# con-som.net
KiCad netlist of a schematic drawn in Altium Designer
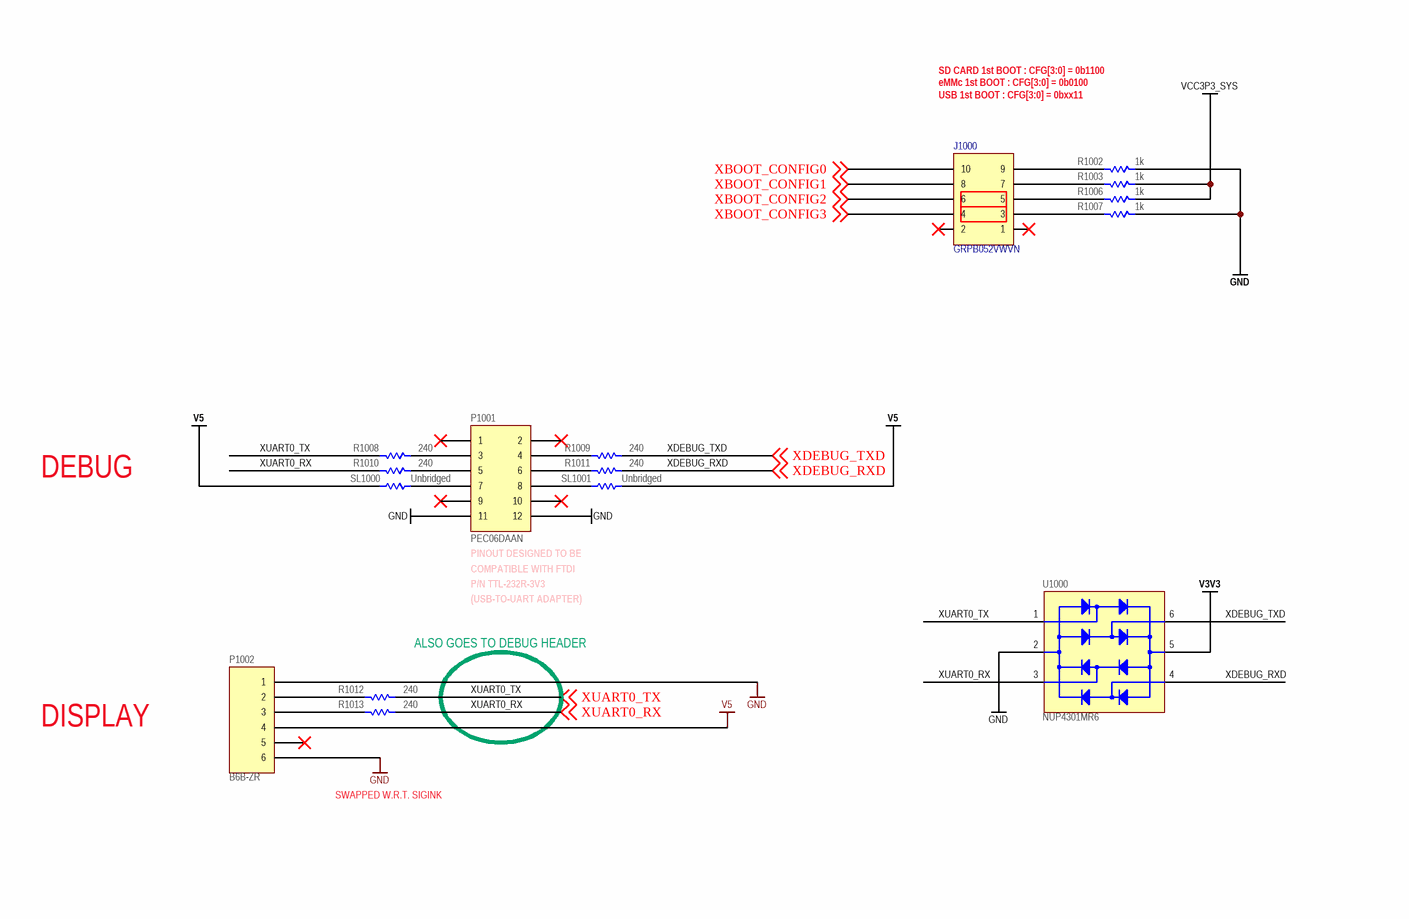
[diagram p0: con-som.SchDoc, top left]
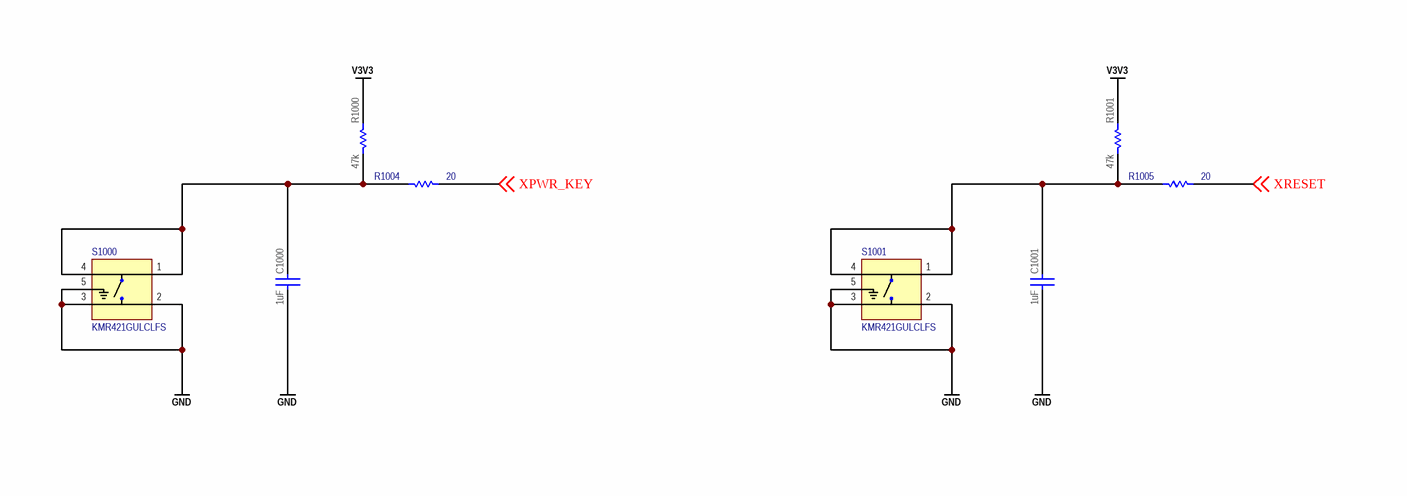
[diagram p1: con-som.SchDoc, top right]
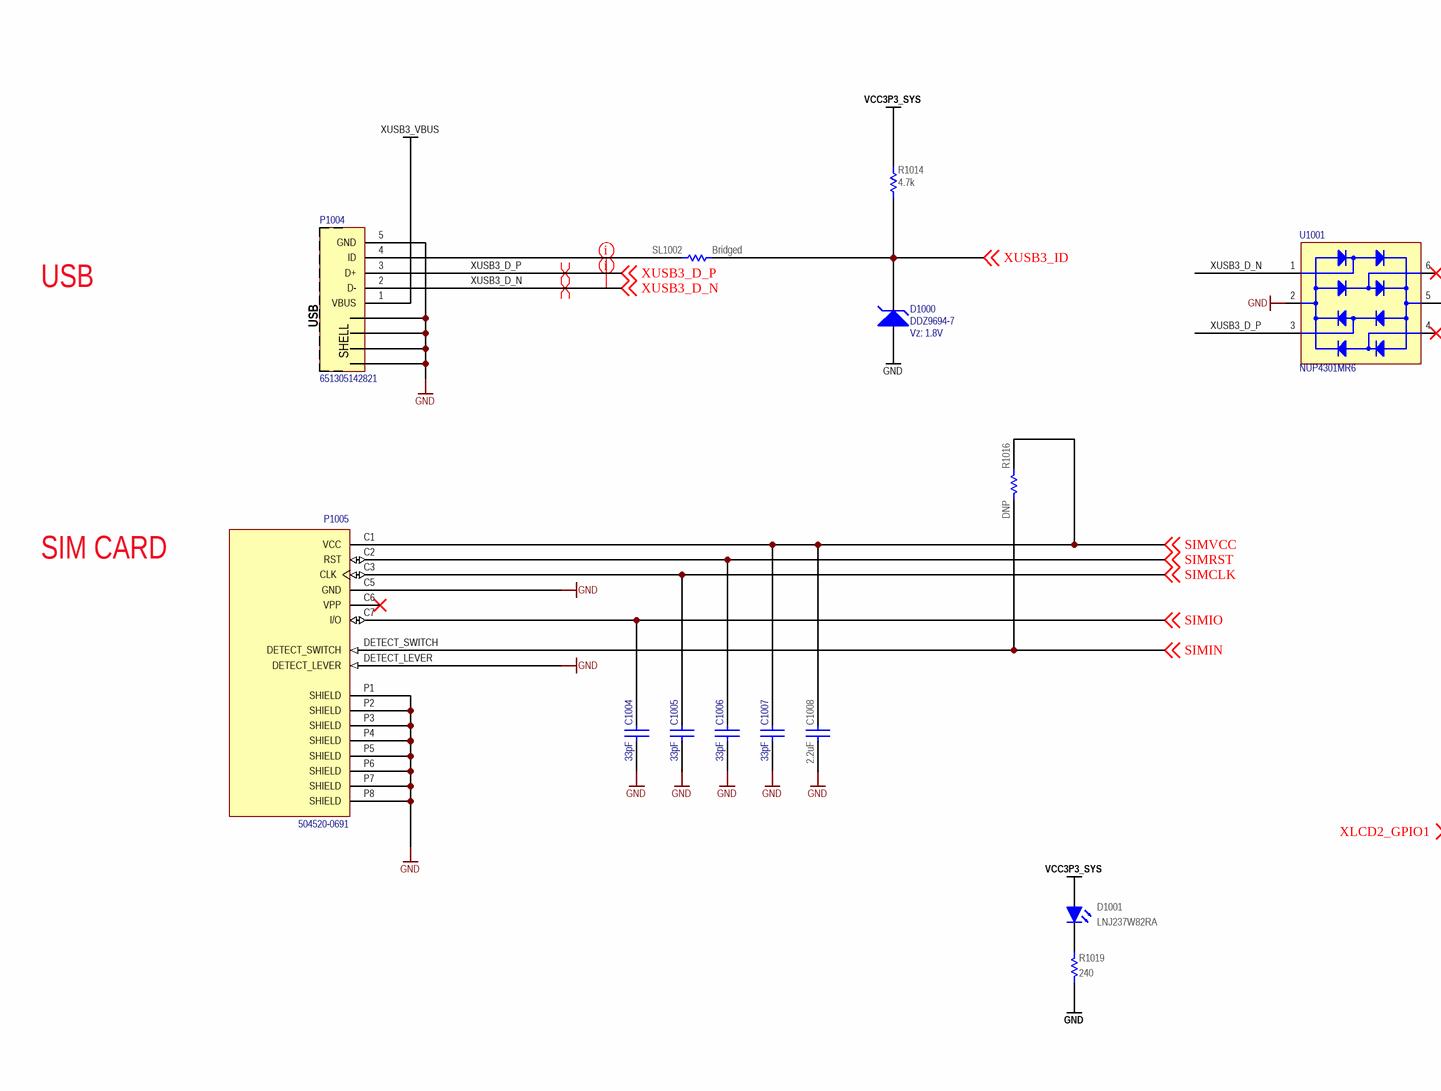
[diagram p2: con-som.SchDoc, bottom left]
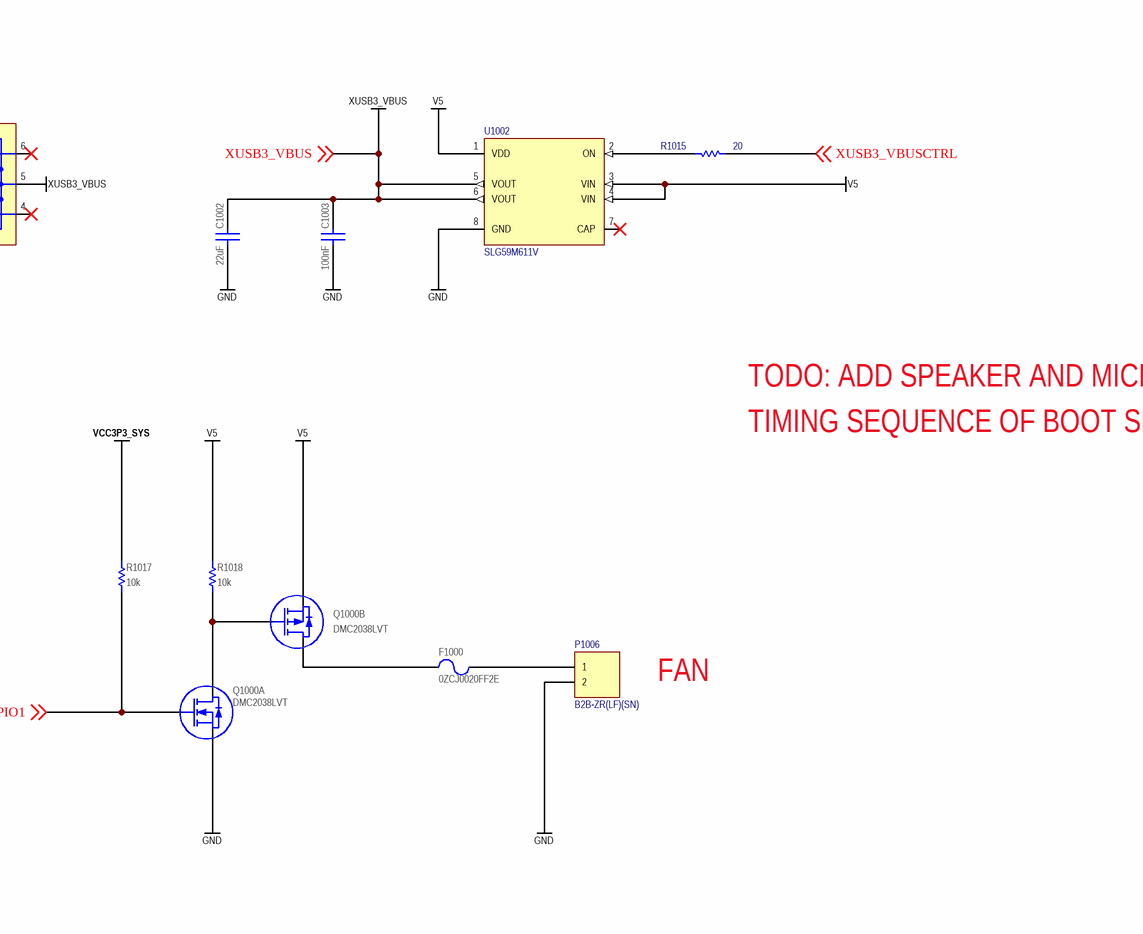
[diagram p3: con-som.SchDoc, bottom right]

(export (version "E")
  (design (tool "Eeschema 10.0.6"))
  (components
    (comp (ref "C1000")
      (value "1uF")
      (footprint "CAPC160X80X90L20N")
      (description "Ceramic Capacitor 1uF ±20% 10V X7R 0603")
      (fields (field (name "MANUFACTURER") "TDK") (field (name "TOLERANCE") "±20%"))
      (libsource (lib "generic") (part "CAP"))
    )
    (comp (ref "C1001")
      (value "1uF")
      (footprint "CAPC160X80X90L20N")
      (description "Ceramic Capacitor 1uF ±20% 10V X7R 0603")
      (fields (field (name "MANUFACTURER") "TDK") (field (name "TOLERANCE") "±20%"))
      (libsource (lib "generic") (part "CAP"))
    )
    (comp (ref "C1002")
      (value "22uF")
      (footprint "CAPC200X125X145L45N")
      (description "Ceramic Capacitor 22uF ±20% 10V X7S 0805")
      (fields (field (name "MANUFACTURER") "TDK") (field (name "TOLERANCE") "±20%"))
      (libsource (lib "generic") (part "CAP"))
    )
    (comp (ref "C1003")
      (value "100nF")
      (footprint "CAPC100X50X55L25N")
      (description "Ceramic Capacitor 100nF ±10% 50V X7R 0402")
      (fields (field (name "MANUFACTURER") "Murata") (field (name "TOLERANCE") "±10%"))
      (libsource (lib "generic") (part "CAP"))
    )
    (comp (ref "C1004")
      (value "33pF")
      (footprint "0402")
      (description "Ceramic Capacitor 33pF ±1% 50V NP0 0402")
      (fields (field (name "VOLTAGE") "50V") (field (name "MANUFACTURER") "Kemet"))
      (libsource (lib "Graviton") (part "CAP 0603"))
    )
    (comp (ref "C1005")
      (value "33pF")
      (footprint "0402")
      (description "Ceramic Capacitor 33pF ±1% 50V NP0 0402")
      (fields (field (name "VOLTAGE") "50V") (field (name "MANUFACTURER") "Kemet"))
      (libsource (lib "Graviton") (part "CAP 0603"))
    )
    (comp (ref "C1006")
      (value "33pF")
      (footprint "0402")
      (description "Ceramic Capacitor 33pF ±1% 50V NP0 0402")
      (fields (field (name "VOLTAGE") "50V") (field (name "MANUFACTURER") "Kemet"))
      (libsource (lib "Graviton") (part "CAP 0603"))
    )
    (comp (ref "C1007")
      (value "33pF")
      (footprint "0402")
      (description "Ceramic Capacitor 33pF ±1% 50V NP0 0402")
      (fields (field (name "VOLTAGE") "50V") (field (name "MANUFACTURER") "Kemet"))
      (libsource (lib "Graviton") (part "CAP 0603"))
    )
    (comp (ref "C1008")
      (value "2.2uF")
      (footprint "CAPC160X80X90L20N")
      (description "Ceramic Capacitor 2.2uF ±20% 10V X7R 0603")
      (fields (field (name "MANUFACTURER") "TDK") (field (name "TOLERANCE") "±20%"))
      (libsource (lib "generic") (part "CAP"))
    )
    (comp (ref "D1000")
      (value "DDZ9694-7")
      (footprint "generic:SOD123")
      (description "Zener Diode 1.8V 500mW SOD123")
      (fields (field (name "MANUFACTURER") "Diodes, Inc.") (field (name "VZ") "1.8V"))
      (libsource (lib "diodes_inc") (part "DDZ9694-7"))
    )
    (comp (ref "D1001")
      (value "LNJ237W82RA")
      (footprint "0603_LED")
      (description "LED, SMT 0603, Color Red, 5mA, 1.85V")
      (fields (field (name "MANUFACTURER") "Panasonic"))
      (libsource (lib "generic") (part "LED0603RD"))
    )
    (comp (ref "F1000")
      (value "0ZCJ0020FF2E")
      (footprint "generic:1206")
      (description "PTC Resettable Fuse, 0.2A, 30V, SMD 1206")
      (fields (field (name "MANUFACTURER") "Bell Fuse"))
      (libsource (lib "bel-fuse") (part "0ZCJ0020FF2E"))
    )
    (comp (ref "J1000")
      (value "GRPB052VWVN")
      (footprint "sullins:GRPB052VWVN")
      (description "Male Header, 0.050\" Pitch, 2x5 Position")
      (fields (field (name "MANUFACTURER") "Sullins"))
      (libsource (lib "sullins") (part "GRPB052VWVN"))
    )
    (comp (ref "P1001")
      (value "PEC06DAAN")
      (footprint "HDR2X6")
      (description "Header, 6-Pin, Dual row")
      (fields (field (name "MANUFACTURER") "Sullins"))
      (libsource (lib "Miscellaneous Connectors") (part "Header 6X2H"))
    )
    (comp (ref "P1002")
      (value "B6B-ZR")
      (footprint "B6B-ZR")
      (description "Header, 6-Pin, Single row, Vertical")
      (fields (field (name "MANUFACTURER") "JST"))
      (libsource (lib "Sigink") (part "TBD"))
    )
    (comp (ref "P1004")
      (value "651305142821")
      (footprint "651305142821")
      (description "Right Angle SMT USB Type-AB Connector Receptacle")
      (fields (field (name "MANUFACTURER") "Wurth Elektronik"))
      (libsource (lib "wurth") (part "651305142821"))
    )
    (comp (ref "P1005")
      (value "504520-0691")
      (footprint "504520-0691")
      (description "micro-SIM Card Connector")
      (fields (field (name "MANUFACTURER") "Molex"))
      (libsource (lib "molex") (part "504520-0691"))
    )
    (comp (ref "P1006")
      (value "B2B-ZR(LF)(SN)")
      (footprint "B2B-ZR")
      (description "Header, 2-Pin")
      (fields (field (name "MANUFACTURER") "JST"))
      (libsource (lib "Miscellaneous Connectors") (part "Header 2"))
    )
    (comp (ref "Q1000")
      (value "DMC2038LVT")
      (footprint "generic:TSOP-6")
      (description "Complementary MOSFET Pair")
      (fields (field (name "MANUFACTURER") "Diodes, Inc."))
      (libsource (lib "") (part "DMC2038LVT_1"))
    )
    (comp (ref "R1000")
      (value "47k")
      (footprint "RESC1005X40N")
      (description "Thick Film Resistor 47k ±1% 0.1W 75V 0402")
      (fields (field (name "TOLERANCE") "±1%") (field (name "MANUFACTURER") "Panasonic"))
      (libsource (lib "generic") (part "RES"))
    )
    (comp (ref "R1001")
      (value "47k")
      (footprint "RESC1005X40N")
      (description "Thick Film Resistor 47k ±1% 0.1W 75V 0402")
      (fields (field (name "TOLERANCE") "±1%") (field (name "MANUFACTURER") "Panasonic"))
      (libsource (lib "generic") (part "RES"))
    )
    (comp (ref "R1002")
      (value "1k")
      (footprint "RESC1005X40N")
      (description "Thick Film Resistor 1k ±1% 0.1W 0402")
      (fields (field (name "TOLERANCE") "±1%") (field (name "MANUFACTURER") "Panasonic"))
      (libsource (lib "generic") (part "RES"))
    )
    (comp (ref "R1003")
      (value "1k")
      (footprint "RESC1005X40N")
      (description "Thick Film Resistor 1k ±1% 0.1W 0402")
      (fields (field (name "TOLERANCE") "±1%") (field (name "MANUFACTURER") "Panasonic"))
      (libsource (lib "generic") (part "RES"))
    )
    (comp (ref "R1004")
      (value "20")
      (footprint "generic:0402")
      (description "Thick Film Resistor 20 ±1% 0402")
      (fields (field (name "MANUFACTURER") "Panasonic") (field (name "TOLERANCE") "±1%"))
      (libsource (lib "altium-import") (part "root_2_mirrored_RES 0402_"))
    )
    (comp (ref "R1005")
      (value "20")
      (footprint "generic:0402")
      (description "Thick Film Resistor 20 ±1% 0402")
      (fields (field (name "MANUFACTURER") "Panasonic") (field (name "TOLERANCE") "±1%"))
      (libsource (lib "altium-import") (part "root_2_mirrored_RES 0402_"))
    )
    (comp (ref "R1006")
      (value "1k")
      (footprint "RESC1005X40N")
      (description "Thick Film Resistor 1k ±1% 0.1W 0402")
      (fields (field (name "TOLERANCE") "±1%") (field (name "MANUFACTURER") "Panasonic"))
      (libsource (lib "generic") (part "RES"))
    )
    (comp (ref "R1007")
      (value "1k")
      (footprint "RESC1005X40N")
      (description "Thick Film Resistor 1k ±1% 0.1W 0402")
      (fields (field (name "TOLERANCE") "±1%") (field (name "MANUFACTURER") "Panasonic"))
      (libsource (lib "generic") (part "RES"))
    )
    (comp (ref "R1008")
      (value "240")
      (footprint "RESC1005X40N")
      (description "Thick Film Resistor 240 ±1% 0.1W 75V 0402")
      (fields (field (name "TOLERANCE") "±1%") (field (name "MANUFACTURER") "Panasonic"))
      (libsource (lib "generic") (part "RES"))
    )
    (comp (ref "R1009")
      (value "240")
      (footprint "RESC1005X40N")
      (description "Thick Film Resistor 240 ±1% 0.1W 75V 0402")
      (fields (field (name "TOLERANCE") "±1%") (field (name "MANUFACTURER") "Panasonic"))
      (libsource (lib "generic") (part "RES"))
    )
    (comp (ref "R1010")
      (value "240")
      (footprint "RESC1005X40N")
      (description "Thick Film Resistor 240 ±1% 0.1W 75V 0402")
      (fields (field (name "TOLERANCE") "±1%") (field (name "MANUFACTURER") "Panasonic"))
      (libsource (lib "generic") (part "RES"))
    )
    (comp (ref "R1011")
      (value "240")
      (footprint "RESC1005X40N")
      (description "Thick Film Resistor 240 ±1% 0.1W 75V 0402")
      (fields (field (name "TOLERANCE") "±1%") (field (name "MANUFACTURER") "Panasonic"))
      (libsource (lib "generic") (part "RES"))
    )
    (comp (ref "R1012")
      (value "240")
      (footprint "RESC1005X40N")
      (description "Thick Film Resistor 240 ±1% 0.1W 75V 0402")
      (fields (field (name "TOLERANCE") "±1%") (field (name "MANUFACTURER") "Panasonic"))
      (libsource (lib "generic") (part "RES"))
    )
    (comp (ref "R1013")
      (value "240")
      (footprint "RESC1005X40N")
      (description "Thick Film Resistor 240 ±1% 0.1W 75V 0402")
      (fields (field (name "TOLERANCE") "±1%") (field (name "MANUFACTURER") "Panasonic"))
      (libsource (lib "generic") (part "RES"))
    )
    (comp (ref "R1014")
      (value "4.7k")
      (footprint "RESC1005X40N")
      (description "Thick Film Resistor 4.7k ±1% 0.1W 75V 0402")
      (fields (field (name "TOLERANCE") "±1%") (field (name "MANUFACTURER") "Panasonic"))
      (libsource (lib "generic") (part "RES"))
    )
    (comp (ref "R1015")
      (value "20")
      (footprint "generic:0402")
      (description "Thick Film Resistor 20 ±1% 0402")
      (fields (field (name "MANUFACTURER") "Panasonic") (field (name "TOLERANCE") "±1%"))
      (libsource (lib "altium-import") (part "root_2_mirrored_RES 0402_"))
    )
    (comp (ref "R1016")
      (value "ERJ-2RKF4702X")
      (footprint "RESC1005X40N")
      (description "Thick Film Resistor 47k ±1% 0.1W 75V 0402")
      (fields
        (field (name "TOLERANCE") "±1%")
        (field (name "MANUFACTURER") "Panasonic")
        (field (name "DO NOT PLACE") "DNP")
      )
      (libsource (lib "generic") (part "RES"))
    )
    (comp (ref "R1017")
      (value "10k")
      (footprint "RESC1005X40N")
      (description "Thick Film Resistor 10k ±1% 0.1W 0402")
      (fields (field (name "MANUFACTURER") "Panasonic") (field (name "TOLERANCE") "±1%"))
      (libsource (lib "generic") (part "RES"))
    )
    (comp (ref "R1018")
      (value "10k")
      (footprint "RESC1005X40N")
      (description "Thick Film Resistor 10k ±1% 0.1W 0402")
      (fields (field (name "MANUFACTURER") "Panasonic") (field (name "TOLERANCE") "±1%"))
      (libsource (lib "generic") (part "RES"))
    )
    (comp (ref "R1019")
      (value "240")
      (footprint "RESC1005X40N")
      (description "Thick Film Resistor 240 ±1% 0.1W 75V 0402")
      (fields (field (name "TOLERANCE") "±1%") (field (name "MANUFACTURER") "Panasonic"))
      (libsource (lib "generic") (part "RES"))
    )
    (comp (ref "S1000")
      (value "KMR421GULCLFS")
      (footprint "SW_KMR421GULCLFS")
      (description "Switch Tactile N.O. SPST Round Button Gull Wing 0.05A 32VDC 1VA 200000Cycles 2N SMD Automotive T/R")
      (fields (field (name "MANUFACTURER") "C&K Components"))
      (libsource (lib "c&k") (part "KMR421GULCLFS"))
    )
    (comp (ref "S1001")
      (value "KMR421GULCLFS")
      (footprint "SW_KMR421GULCLFS")
      (description "Switch Tactile N.O. SPST Round Button Gull Wing 0.05A 32VDC 1VA 200000Cycles 2N SMD Automotive T/R")
      (fields (field (name "MANUFACTURER") "C&K Components"))
      (libsource (lib "c&k") (part "KMR421GULCLFS"))
    )
    (comp (ref "SL1000")
      (value "Unbridged")
      (footprint "SOLDERLINK0603X26N")
      (description "Solder Link Unbridged")
      (fields (field (name "Comment") "SOLDER_LINK"))
      (libsource (lib "generic") (part "RES"))
    )
    (comp (ref "SL1001")
      (value "Unbridged")
      (footprint "SOLDERLINK0603X26N")
      (description "Solder Link Unbridged")
      (fields (field (name "Comment") "SOLDER_LINK"))
      (libsource (lib "generic") (part "RES"))
    )
    (comp (ref "SL1002")
      (value "Bridged")
      (footprint "SOLDERLINK0603X26N_BRIDGED")
      (description "Solder Link Bridged")
      (fields (field (name "Comment") "SOLDER_LINK_BRIDGED"))
      (libsource (lib "generic") (part "RES"))
    )
    (comp (ref "U1000")
      (value "NUP4301MR6")
      (footprint "generic:SOT23-6")
      (description "4-Lane TVS Diode Array")
      (fields (field (name "MANUFACTURER") "On Semiconductor"))
      (libsource (lib "on_semi") (part "NUP4301MR6"))
    )
    (comp (ref "U1001")
      (value "NUP4301MR6")
      (footprint "generic:SOT23-6")
      (description "4-Lane TVS Diode Array")
      (fields (field (name "MANUFACTURER") "On Semiconductor"))
      (libsource (lib "on_semi") (part "NUP4301MR6"))
    )
    (comp (ref "U1002")
      (value "SLG59M611V")
      (footprint "DFN200X150X80-8N")
      (description "High-Side Load Switch")
      (fields (field (name "MANUFACTURER") "Silego"))
      (libsource (lib "silego") (part "SLG59M611V"))
    )
  )
  (nets
    (net (code "1") (name "GND") (class "Default")
      (node (ref "C1000") (pin "1") (pinfunction "1_1") (pintype "passive"))
      (node (ref "C1001") (pin "1") (pinfunction "1_1") (pintype "passive"))
      (node (ref "C1002") (pin "1") (pinfunction "1_1") (pintype "passive"))
      (node (ref "C1003") (pin "1") (pinfunction "1_1") (pintype "passive"))
      (node (ref "C1004") (pin "2") (pinfunction "2_2") (pintype "passive"))
      (node (ref "C1005") (pin "2") (pinfunction "2_2") (pintype "passive"))
      (node (ref "C1006") (pin "2") (pinfunction "2_2") (pintype "passive"))
      (node (ref "C1007") (pin "2") (pinfunction "2_2") (pintype "passive"))
      (node (ref "C1008") (pin "1") (pinfunction "1_1") (pintype "passive"))
      (node (ref "D1000") (pin "1") (pinfunction "A_1") (pintype "power_in"))
      (node (ref "P1001") (pin "11") (pinfunction "11_11") (pintype "passive"))
      (node (ref "P1001") (pin "12") (pinfunction "12_12") (pintype "passive"))
      (node (ref "P1002") (pin "1") (pinfunction "1_1") (pintype "passive"))
      (node (ref "P1002") (pin "6") (pinfunction "6_6") (pintype "passive"))
      (node (ref "P1004") (pin "5") (pinfunction "GND_5") (pintype "passive"))
      (node (ref "P1004") (pin "SHELL") (pinfunction "SHIELD_SHELL") (pintype "passive"))
      (node (ref "P1004") (pin "SHELL1") (pinfunction "SHIELD_SHELL1") (pintype "passive"))
      (node (ref "P1004") (pin "SHELL2") (pinfunction "SHIELD_SHELL2") (pintype "passive"))
      (node (ref "P1004") (pin "SHELL3") (pinfunction "SHIELD_SHELL3") (pintype "passive"))
      (node (ref "P1005") (pin "C5") (pinfunction "GND_C5") (pintype "power_in"))
      (node (ref "P1005") (pin "DETECT_LEVER") (pinfunction "DETECT_LEVER_DETECT_LEVER") (pintype "input"))
      (node (ref "P1005") (pin "P1") (pinfunction "SHIELD_P1") (pintype "passive"))
      (node (ref "P1005") (pin "P2") (pinfunction "SHIELD_P2") (pintype "passive"))
      (node (ref "P1005") (pin "P3") (pinfunction "SHIELD_P3") (pintype "passive"))
      (node (ref "P1005") (pin "P4") (pinfunction "SHIELD_P4") (pintype "passive"))
      (node (ref "P1005") (pin "P5") (pinfunction "SHIELD_P5") (pintype "passive"))
      (node (ref "P1005") (pin "P6") (pinfunction "SHIELD_P6") (pintype "passive"))
      (node (ref "P1005") (pin "P7") (pinfunction "SHIELD_P7") (pintype "passive"))
      (node (ref "P1005") (pin "P8") (pinfunction "SHIELD_P8") (pintype "passive"))
      (node (ref "P1006") (pin "2") (pinfunction "2_2") (pintype "passive"))
      (node (ref "Q1000") (pin "5") (pinfunction "S_5") (pintype "passive"))
      (node (ref "R1002") (pin "2") (pinfunction "2_2") (pintype "passive"))
      (node (ref "R1007") (pin "2") (pinfunction "2_2") (pintype "passive"))
      (node (ref "R1019") (pin "2") (pinfunction "2_2") (pintype "passive"))
      (node (ref "S1000") (pin "2") (pinfunction "2_2") (pintype "passive"))
      (node (ref "S1000") (pin "3") (pinfunction "3_3") (pintype "passive"))
      (node (ref "S1000") (pin "5") (pinfunction "G_5") (pintype "power_in"))
      (node (ref "S1001") (pin "2") (pinfunction "2_2") (pintype "passive"))
      (node (ref "S1001") (pin "3") (pinfunction "3_3") (pintype "passive"))
      (node (ref "S1001") (pin "5") (pinfunction "G_5") (pintype "power_in"))
      (node (ref "U1000") (pin "2") (pinfunction "VN_2") (pintype "passive"))
      (node (ref "U1001") (pin "2") (pinfunction "VN_2") (pintype "passive"))
      (node (ref "U1002") (pin "8") (pinfunction "GND_8") (pintype "power_in"))
    )
    (net (code "2") (name "Net-(C1000-Pad2)") (class "Default")
      (node (ref "C1000") (pin "2") (pinfunction "2_2") (pintype "passive"))
      (node (ref "R1000") (pin "1") (pinfunction "1_1") (pintype "passive"))
      (node (ref "R1004") (pin "1") (pinfunction "1_1") (pintype "passive"))
      (node (ref "S1000") (pin "1") (pinfunction "1_1") (pintype "passive"))
      (node (ref "S1000") (pin "4") (pinfunction "4_4") (pintype "passive"))
    )
    (net (code "3") (name "Net-(C1001-Pad2)") (class "Default")
      (node (ref "C1001") (pin "2") (pinfunction "2_2") (pintype "passive"))
      (node (ref "R1001") (pin "1") (pinfunction "1_1") (pintype "passive"))
      (node (ref "R1005") (pin "1") (pinfunction "1_1") (pintype "passive"))
      (node (ref "S1001") (pin "1") (pinfunction "1_1") (pintype "passive"))
      (node (ref "S1001") (pin "4") (pinfunction "4_4") (pintype "passive"))
    )
    (net (code "4") (name "Net-(D1001-K)") (class "Default")
      (node (ref "D1001") (pin "2") (pinfunction "K_2") (pintype "passive"))
      (node (ref "R1019") (pin "1") (pinfunction "1_1") (pintype "passive"))
    )
    (net (code "5") (name "Net-(F1000-Pad2)") (class "Default")
      (node (ref "F1000") (pin "2") (pinfunction "2_2") (pintype "passive"))
      (node (ref "P1006") (pin "1") (pinfunction "1_1") (pintype "passive"))
    )
    (net (code "6") (name "Net-(J1000-Pad3)") (class "Default")
      (node (ref "J1000") (pin "3") (pinfunction "3_3") (pintype "passive"))
      (node (ref "R1007") (pin "1") (pinfunction "1_1") (pintype "passive"))
    )
    (net (code "7") (name "Net-(J1000-Pad5)") (class "Default")
      (node (ref "J1000") (pin "5") (pinfunction "5_5") (pintype "passive"))
      (node (ref "R1006") (pin "1") (pinfunction "1_1") (pintype "passive"))
    )
    (net (code "8") (name "Net-(J1000-Pad7)") (class "Default")
      (node (ref "J1000") (pin "7") (pinfunction "7_7") (pintype "passive"))
      (node (ref "R1003") (pin "1") (pinfunction "1_1") (pintype "passive"))
    )
    (net (code "9") (name "Net-(J1000-Pad9)") (class "Default")
      (node (ref "J1000") (pin "9") (pinfunction "9_9") (pintype "passive"))
      (node (ref "R1002") (pin "1") (pinfunction "1_1") (pintype "passive"))
    )
    (net (code "10") (name "Net-(P1001-Pad3)") (class "Default")
      (node (ref "P1001") (pin "3") (pinfunction "3_3") (pintype "passive"))
      (node (ref "R1008") (pin "2") (pinfunction "2_2") (pintype "passive"))
    )
    (net (code "11") (name "Net-(P1001-Pad4)") (class "Default")
      (node (ref "P1001") (pin "4") (pinfunction "4_4") (pintype "passive"))
      (node (ref "R1009") (pin "1") (pinfunction "1_1") (pintype "passive"))
    )
    (net (code "12") (name "Net-(P1001-Pad5)") (class "Default")
      (node (ref "P1001") (pin "5") (pinfunction "5_5") (pintype "passive"))
      (node (ref "R1010") (pin "2") (pinfunction "2_2") (pintype "passive"))
    )
    (net (code "13") (name "Net-(P1001-Pad6)") (class "Default")
      (node (ref "P1001") (pin "6") (pinfunction "6_6") (pintype "passive"))
      (node (ref "R1011") (pin "1") (pinfunction "1_1") (pintype "passive"))
    )
    (net (code "14") (name "Net-(P1001-Pad7)") (class "Default")
      (node (ref "P1001") (pin "7") (pinfunction "7_7") (pintype "passive"))
      (node (ref "SL1000") (pin "2") (pinfunction "2_2") (pintype "passive"))
    )
    (net (code "15") (name "Net-(P1001-Pad8)") (class "Default")
      (node (ref "P1001") (pin "8") (pinfunction "8_8") (pintype "passive"))
      (node (ref "SL1001") (pin "1") (pinfunction "1_1") (pintype "passive"))
    )
    (net (code "16") (name "Net-(P1002-Pad2)") (class "Default")
      (node (ref "P1002") (pin "2") (pinfunction "2_2") (pintype "passive"))
      (node (ref "R1012") (pin "1") (pinfunction "1_1") (pintype "passive"))
    )
    (net (code "17") (name "Net-(P1002-Pad3)") (class "Default")
      (node (ref "P1002") (pin "3") (pinfunction "3_3") (pintype "passive"))
      (node (ref "R1013") (pin "1") (pinfunction "1_1") (pintype "passive"))
    )
    (net (code "18") (name "Net-(P1004-ID)") (class "Default")
      (node (ref "P1004") (pin "4") (pinfunction "ID_4") (pintype "passive"))
      (node (ref "SL1002") (pin "1") (pinfunction "1_1") (pintype "passive"))
    )
    (net (code "19") (name "Net-(Q1000A-D)") (class "Default")
      (node (ref "Q1000") (pin "3") (pinfunction "G_3") (pintype "passive"))
      (node (ref "Q1000") (pin "6") (pinfunction "D_6") (pintype "passive"))
      (node (ref "R1018") (pin "1") (pinfunction "1_1") (pintype "passive"))
    )
    (net (code "20") (name "Net-(Q1000B-D)") (class "Default")
      (node (ref "F1000") (pin "1") (pinfunction "1_1") (pintype "passive"))
      (node (ref "Q1000") (pin "4") (pinfunction "D_4") (pintype "passive"))
    )
    (net (code "21") (name "Net-(U1002-ON)") (class "Default")
      (node (ref "R1015") (pin "1") (pinfunction "1_1") (pintype "passive"))
      (node (ref "U1002") (pin "2") (pinfunction "ON_2") (pintype "input"))
    )
    (net (code "22") (name "SIMCLK") (class "Default")
      (node (ref "C1005") (pin "1") (pinfunction "1_1") (pintype "passive"))
      (node (ref "P1005") (pin "C3") (pinfunction "CLK_C3") (pintype "bidirectional"))
    )
    (net (code "23") (name "SIMIN") (class "Default")
      (node (ref "P1005") (pin "DETECT_SWITCH") (pinfunction "DETECT_SWITCH_DETECT_SWITCH") (pintype "input"))
      (node (ref "R1016") (pin "1") (pinfunction "1_1") (pintype "passive"))
    )
    (net (code "24") (name "SIMIO") (class "Default")
      (node (ref "C1004") (pin "1") (pinfunction "1_1") (pintype "passive"))
      (node (ref "P1005") (pin "C7") (pinfunction "I/O_C7") (pintype "bidirectional"))
    )
    (net (code "25") (name "SIMRST") (class "Default")
      (node (ref "C1006") (pin "1") (pinfunction "1_1") (pintype "passive"))
      (node (ref "P1005") (pin "C2") (pinfunction "RST_C2") (pintype "bidirectional"))
    )
    (net (code "26") (name "SIMVCC") (class "Default")
      (node (ref "C1007") (pin "1") (pinfunction "1_1") (pintype "passive"))
      (node (ref "C1008") (pin "2") (pinfunction "2_2") (pintype "passive"))
      (node (ref "P1005") (pin "C1") (pinfunction "VCC_C1") (pintype "power_in"))
      (node (ref "R1016") (pin "2") (pinfunction "2_2") (pintype "passive"))
    )
    (net (code "27") (name "V3V3") (class "Default")
      (node (ref "R1000") (pin "2") (pinfunction "2_2") (pintype "passive"))
      (node (ref "R1001") (pin "2") (pinfunction "2_2") (pintype "passive"))
      (node (ref "U1000") (pin "5") (pinfunction "VP_5") (pintype "passive"))
    )
    (net (code "28") (name "V5") (class "Default")
      (node (ref "P1002") (pin "4") (pinfunction "4_4") (pintype "passive"))
      (node (ref "Q1000") (pin "2") (pinfunction "S_2") (pintype "passive"))
      (node (ref "R1018") (pin "2") (pinfunction "2_2") (pintype "passive"))
      (node (ref "SL1000") (pin "1") (pinfunction "1_1") (pintype "passive"))
      (node (ref "SL1001") (pin "2") (pinfunction "2_2") (pintype "passive"))
      (node (ref "U1002") (pin "1") (pinfunction "VDD_1") (pintype "power_in"))
      (node (ref "U1002") (pin "3") (pinfunction "VIN_3") (pintype "input"))
      (node (ref "U1002") (pin "4") (pinfunction "VIN_4") (pintype "input"))
    )
    (net (code "29") (name "VCC3P3_SYS") (class "Default")
      (node (ref "D1001") (pin "1") (pinfunction "A_1") (pintype "passive"))
      (node (ref "R1003") (pin "2") (pinfunction "2_2") (pintype "passive"))
      (node (ref "R1006") (pin "2") (pinfunction "2_2") (pintype "passive"))
      (node (ref "R1014") (pin "2") (pinfunction "2_2") (pintype "passive"))
      (node (ref "R1017") (pin "2") (pinfunction "2_2") (pintype "passive"))
    )
    (net (code "30") (name "XBOOT_CONFIG0") (class "Default")
      (node (ref "J1000") (pin "10") (pinfunction "10_10") (pintype "passive"))
    )
    (net (code "31") (name "XBOOT_CONFIG1") (class "Default")
      (node (ref "J1000") (pin "8") (pinfunction "8_8") (pintype "passive"))
    )
    (net (code "32") (name "XBOOT_CONFIG2") (class "Default")
      (node (ref "J1000") (pin "6") (pinfunction "6_6") (pintype "passive"))
    )
    (net (code "33") (name "XBOOT_CONFIG3") (class "Default")
      (node (ref "J1000") (pin "4") (pinfunction "4_4") (pintype "passive"))
    )
    (net (code "34") (name "XDEBUG_RXD") (class "Default")
      (node (ref "R1011") (pin "2") (pinfunction "2_2") (pintype "passive"))
      (node (ref "U1000") (pin "4") (pinfunction "C_4") (pintype "passive"))
    )
    (net (code "35") (name "XDEBUG_TXD") (class "Default")
      (node (ref "R1009") (pin "2") (pinfunction "2_2") (pintype "passive"))
      (node (ref "U1000") (pin "6") (pinfunction "D_6") (pintype "passive"))
    )
    (net (code "36") (name "XLCD2_GPIO1") (class "Default")
      (node (ref "Q1000") (pin "1") (pinfunction "G_1") (pintype "passive"))
      (node (ref "R1017") (pin "1") (pinfunction "1_1") (pintype "passive"))
    )
    (net (code "37") (name "XPWR_KEY") (class "Default")
      (node (ref "R1004") (pin "2") (pinfunction "2_2") (pintype "passive"))
    )
    (net (code "38") (name "XRESET") (class "Default")
      (node (ref "R1005") (pin "2") (pinfunction "2_2") (pintype "passive"))
    )
    (net (code "39") (name "XUART0_RX") (class "Default")
      (node (ref "R1010") (pin "1") (pinfunction "1_1") (pintype "passive"))
      (node (ref "R1013") (pin "2") (pinfunction "2_2") (pintype "passive"))
      (node (ref "U1000") (pin "3") (pinfunction "B_3") (pintype "passive"))
    )
    (net (code "40") (name "XUART0_TX") (class "Default")
      (node (ref "R1008") (pin "1") (pinfunction "1_1") (pintype "passive"))
      (node (ref "R1012") (pin "2") (pinfunction "2_2") (pintype "passive"))
      (node (ref "U1000") (pin "1") (pinfunction "A_1") (pintype "passive"))
    )
    (net (code "41") (name "XUSB3_D_N") (class "Default")
      (node (ref "P1004") (pin "2") (pinfunction "D-_2") (pintype "passive"))
      (node (ref "U1001") (pin "1") (pinfunction "A_1") (pintype "passive"))
    )
    (net (code "42") (name "XUSB3_D_P") (class "Default")
      (node (ref "P1004") (pin "3") (pinfunction "D+_3") (pintype "passive"))
      (node (ref "U1001") (pin "3") (pinfunction "B_3") (pintype "passive"))
    )
    (net (code "43") (name "XUSB3_ID") (class "Default")
      (node (ref "D1000") (pin "2") (pinfunction "C_2") (pintype "passive"))
      (node (ref "R1014") (pin "1") (pinfunction "1_1") (pintype "passive"))
      (node (ref "SL1002") (pin "2") (pinfunction "2_2") (pintype "passive"))
    )
    (net (code "44") (name "XUSB3_VBUS") (class "Default")
      (node (ref "C1002") (pin "2") (pinfunction "2_2") (pintype "passive"))
      (node (ref "C1003") (pin "2") (pinfunction "2_2") (pintype "passive"))
      (node (ref "P1004") (pin "1") (pinfunction "VBUS_1") (pintype "passive"))
      (node (ref "U1001") (pin "5") (pinfunction "VP_5") (pintype "passive"))
      (node (ref "U1002") (pin "5") (pinfunction "VOUT_5") (pintype "output"))
      (node (ref "U1002") (pin "6") (pinfunction "VOUT_6") (pintype "output"))
    )
    (net (code "45") (name "XUSB3_VBUSCTRL") (class "Default")
      (node (ref "R1015") (pin "2") (pinfunction "2_2") (pintype "passive"))
    )
    (net (code "46") (name "unconnected-(J1000-Pad1)") (class "Default")
      (node (ref "J1000") (pin "1") (pinfunction "1_1") (pintype "passive+no_connect"))
    )
    (net (code "47") (name "unconnected-(J1000-Pad2)") (class "Default")
      (node (ref "J1000") (pin "2") (pinfunction "2_2") (pintype "passive+no_connect"))
    )
    (net (code "48") (name "unconnected-(P1001-Pad1)") (class "Default")
      (node (ref "P1001") (pin "1") (pinfunction "1_1") (pintype "passive+no_connect"))
    )
    (net (code "49") (name "unconnected-(P1001-Pad2)") (class "Default")
      (node (ref "P1001") (pin "2") (pinfunction "2_2") (pintype "passive+no_connect"))
    )
    (net (code "50") (name "unconnected-(P1001-Pad9)") (class "Default")
      (node (ref "P1001") (pin "9") (pinfunction "9_9") (pintype "passive+no_connect"))
    )
    (net (code "51") (name "unconnected-(P1001-Pad10)") (class "Default")
      (node (ref "P1001") (pin "10") (pinfunction "10_10") (pintype "passive+no_connect"))
    )
    (net (code "52") (name "unconnected-(P1002-Pad5)") (class "Default")
      (node (ref "P1002") (pin "5") (pinfunction "5_5") (pintype "passive+no_connect"))
    )
    (net (code "53") (name "unconnected-(P1005-VPP-PadC6)") (class "Default")
      (node (ref "P1005") (pin "C6") (pinfunction "VPP_C6") (pintype "power_in+no_connect"))
    )
    (net (code "54") (name "unconnected-(U1001-C-Pad4)") (class "Default")
      (node (ref "U1001") (pin "4") (pinfunction "C_4") (pintype "passive+no_connect"))
    )
    (net (code "55") (name "unconnected-(U1001-D-Pad6)") (class "Default")
      (node (ref "U1001") (pin "6") (pinfunction "D_6") (pintype "passive+no_connect"))
    )
    (net (code "56") (name "unconnected-(U1002-CAP-Pad7)") (class "Default")
      (node (ref "U1002") (pin "7") (pinfunction "CAP_7") (pintype "passive+no_connect"))
    )
  )
)
